# LaserConverterBoard.net
KiCad netlist of a schematic drawn in EAGLE
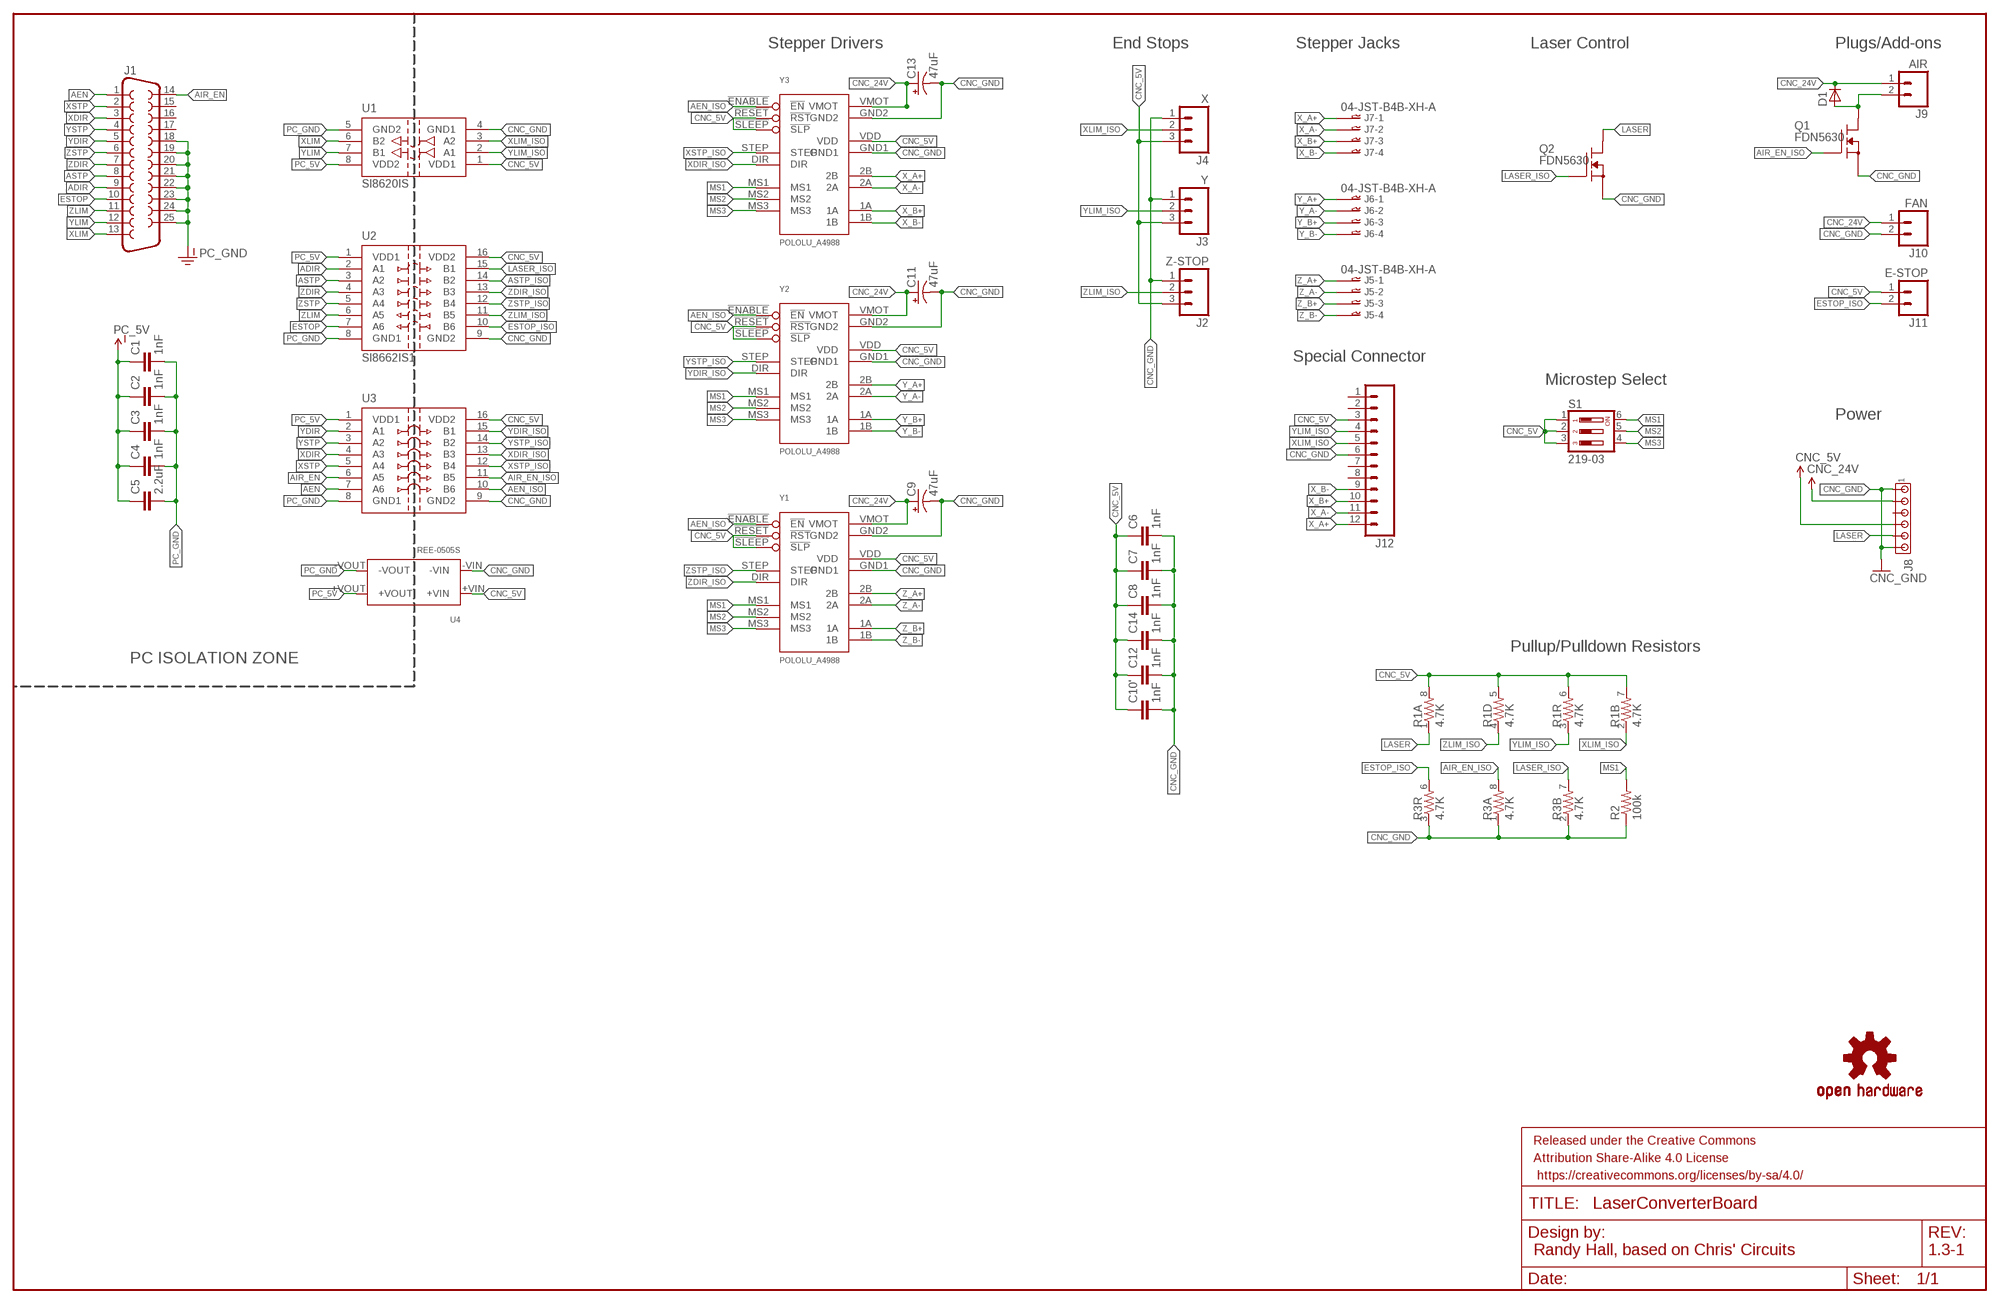
[diagram p0: schematic, sheet 1]

(export (version "E")
  (design (tool "Eeschema 10.0.6"))
  (components
    (comp (ref "C1")
      (value "1nF")
      (footprint "eagle-import:0603-CAP")
      (libsource (lib "eagle-import") (part "1NF/1000PF-50V-10%(0603)"))
    )
    (comp (ref "C2")
      (value "1nF")
      (footprint "eagle-import:0603-CAP")
      (libsource (lib "eagle-import") (part "1NF/1000PF-50V-10%(0603)"))
    )
    (comp (ref "C3")
      (value "1nF")
      (footprint "eagle-import:0603-CAP")
      (libsource (lib "eagle-import") (part "1NF/1000PF-50V-10%(0603)"))
    )
    (comp (ref "C4")
      (value "1nF")
      (footprint "eagle-import:0603-CAP")
      (libsource (lib "eagle-import") (part "1NF/1000PF-50V-10%(0603)"))
    )
    (comp (ref "C5")
      (value "2.2uF")
      (footprint "eagle-import:0603-CAP")
      (libsource (lib "eagle-import") (part "1NF/1000PF-50V-10%(0603)"))
    )
    (comp (ref "C6")
      (value "1nF")
      (footprint "eagle-import:0603-CAP")
      (libsource (lib "eagle-import") (part "1NF/1000PF-50V-10%(0603)"))
    )
    (comp (ref "C7")
      (value "1nF")
      (footprint "eagle-import:0603-CAP")
      (libsource (lib "eagle-import") (part "1NF/1000PF-50V-10%(0603)"))
    )
    (comp (ref "C8")
      (value "1nF")
      (footprint "eagle-import:0603-CAP")
      (libsource (lib "eagle-import") (part "1NF/1000PF-50V-10%(0603)"))
    )
    (comp (ref "C9")
      (value "47uF")
      (footprint "eagle-import:PANASONIC_E")
      (libsource (lib "eagle-import") (part "CPOL-USE"))
    )
    (comp (ref "C10'")
      (value "1nF")
      (footprint "eagle-import:0603-CAP")
      (libsource (lib "eagle-import") (part "1NF/1000PF-50V-10%(0603)"))
    )
    (comp (ref "C11")
      (value "47uF")
      (footprint "eagle-import:PANASONIC_E")
      (libsource (lib "eagle-import") (part "CPOL-USE"))
    )
    (comp (ref "C12")
      (value "1nF")
      (footprint "eagle-import:0603-CAP")
      (libsource (lib "eagle-import") (part "1NF/1000PF-50V-10%(0603)"))
    )
    (comp (ref "C13")
      (value "47uF")
      (footprint "eagle-import:PANASONIC_E")
      (libsource (lib "eagle-import") (part "CPOL-USE"))
    )
    (comp (ref "C14")
      (value "1nF")
      (footprint "eagle-import:0603-CAP")
      (libsource (lib "eagle-import") (part "1NF/1000PF-50V-10%(0603)"))
    )
    (comp (ref "D1")
      (value "D-SOD123")
      (footprint "eagle-import:SOD123")
      (libsource (lib "eagle-import") (part "D-SOD123"))
    )
    (comp (ref "FRAME1")
      (value "FRAME-LEDGER")
      (footprint "eagle-import:CREATIVE_COMMONS")
      (libsource (lib "eagle-import") (part "FRAME-LEDGER"))
    )
    (comp (ref "J1")
      (value "F25HP")
      (footprint "eagle-import:F25HP")
      (libsource (lib "eagle-import") (part "F25HP"))
    )
    (comp (ref "J2")
      (value "Z-STOP")
      (footprint "eagle-import:1X03")
      (libsource (lib "eagle-import") (part "M03PTH"))
    )
    (comp (ref "J3")
      (value "Y")
      (footprint "eagle-import:1X03")
      (libsource (lib "eagle-import") (part "M03PTH"))
    )
    (comp (ref "J4")
      (value "X")
      (footprint "eagle-import:1X03")
      (libsource (lib "eagle-import") (part "M03PTH"))
    )
    (comp (ref "J5")
      (value "04-JST-B4B-XH-A")
      (footprint "eagle-import:B4B-XH")
      (libsource (lib "eagle-import") (part "04-JST-B4B-XH-A"))
    )
    (comp (ref "J6")
      (value "04-JST-B4B-XH-A")
      (footprint "eagle-import:B4B-XH")
      (libsource (lib "eagle-import") (part "04-JST-B4B-XH-A"))
    )
    (comp (ref "J7")
      (value "04-JST-B4B-XH-A")
      (footprint "eagle-import:B4B-XH")
      (libsource (lib "eagle-import") (part "04-JST-B4B-XH-A"))
    )
    (comp (ref "J8")
      (value "MTA06-156")
      (footprint "eagle-import:1X6MTA")
      (libsource (lib "eagle-import") (part "MTA06-156"))
    )
    (comp (ref "J9")
      (value "AIR")
      (footprint "eagle-import:1X02")
      (libsource (lib "eagle-import") (part "M02PTH"))
    )
    (comp (ref "J10")
      (value "FAN")
      (footprint "eagle-import:1X02")
      (libsource (lib "eagle-import") (part "M02PTH"))
    )
    (comp (ref "J11")
      (value "E-STOP")
      (footprint "eagle-import:1X02")
      (libsource (lib "eagle-import") (part "M02PTH"))
    )
    (comp (ref "J12")
      (value "M12")
      (footprint "eagle-import:12P")
      (libsource (lib "eagle-import") (part "M12"))
    )
    (comp (ref "LOGO1")
      (value "OSHW-LOGOS")
      (footprint "eagle-import:OSHW-LOGO-S")
      (libsource (lib "eagle-import") (part "OSHW-LOGOS"))
    )
    (comp (ref "Q1")
      (value "FDN5630")
      (footprint "eagle-import:SOT23")
      (libsource (lib "eagle-import") (part "FDN5630"))
    )
    (comp (ref "Q2")
      (value "FDN5630")
      (footprint "eagle-import:SOT23")
      (libsource (lib "eagle-import") (part "FDN5630"))
    )
    (comp (ref "R1")
      (value "4.7K")
      (footprint "eagle-import:0603-ARV")
      (libsource (lib "eagle-import") (part "RESISTOR-ARRAY0603-ARV"))
    )
    (comp (ref "R2")
      (value "100k")
      (footprint "eagle-import:0603-RES")
      (libsource (lib "eagle-import") (part "100KOHM1/10W1%(0603)"))
    )
    (comp (ref "R3")
      (value "4.7K")
      (footprint "eagle-import:0603-ARV")
      (libsource (lib "eagle-import") (part "RESISTOR-ARRAY0603-ARV"))
    )
    (comp (ref "S1")
      (value "219-03")
      (footprint "eagle-import:CTS-219-03")
      (libsource (lib "eagle-import") (part "219-03"))
    )
    (comp (ref "U1")
      (value "SI8620IS")
      (footprint "eagle-import:SO08")
      (libsource (lib "eagle-import") (part "SI8620IS"))
    )
    (comp (ref "U2")
      (value "SI8662IS1")
      (footprint "eagle-import:SO16")
      (libsource (lib "eagle-import") (part "SI8462IS1"))
    )
    (comp (ref "U3")
      (value "SI8460IS1")
      (footprint "eagle-import:SO16")
      (libsource (lib "eagle-import") (part "SI8460IS1"))
    )
    (comp (ref "U4")
      (value "REE-0505S")
      (footprint "eagle-import:SIP7")
      (libsource (lib "eagle-import") (part "REE-0505S"))
    )
    (comp (ref "Y1")
      (value "POLOLU_A4988")
      (footprint "eagle-import:POLOLU_STEPPER_DRIVER")
      (libsource (lib "eagle-import") (part "POLOLU_A4988"))
    )
    (comp (ref "Y2")
      (value "POLOLU_A4988")
      (footprint "eagle-import:POLOLU_STEPPER_DRIVER")
      (libsource (lib "eagle-import") (part "POLOLU_A4988"))
    )
    (comp (ref "Y3")
      (value "POLOLU_A4988")
      (footprint "eagle-import:POLOLU_STEPPER_DRIVER")
      (libsource (lib "eagle-import") (part "POLOLU_A4988"))
    )
  )
  (nets
    (net (code "1") (name "ADIR") (class "Default")
      (node (ref "J1") (pin "9") (pinfunction "9_9") (pintype "passive"))
      (node (ref "U2") (pin "2") (pinfunction "A1_2") (pintype "input"))
    )
    (net (code "2") (name "AEN") (class "Default")
      (node (ref "J1") (pin "1") (pinfunction "1_1") (pintype "passive"))
      (node (ref "U3") (pin "7") (pinfunction "A6_7") (pintype "input"))
    )
    (net (code "3") (name "AEN_ISO") (class "Default")
      (node (ref "U3") (pin "10") (pinfunction "B6_10") (pintype "output"))
      (node (ref "Y1") (pin "!ENABLE") (pinfunction "~{EN}_!ENABLE") (pintype "input"))
      (node (ref "Y2") (pin "!ENABLE") (pinfunction "~{EN}_!ENABLE") (pintype "input"))
      (node (ref "Y3") (pin "!ENABLE") (pinfunction "~{EN}_!ENABLE") (pintype "input"))
    )
    (net (code "4") (name "AIR_EN") (class "Default")
      (node (ref "J1") (pin "14") (pinfunction "14_14") (pintype "passive"))
      (node (ref "U3") (pin "6") (pinfunction "A5_6") (pintype "input"))
    )
    (net (code "5") (name "AIR_EN_ISO") (class "Default")
      (node (ref "Q1") (pin "1") (pinfunction "G_1") (pintype "passive"))
      (node (ref "R3") (pin "8") (pinfunction "2_8") (pintype "passive"))
      (node (ref "U3") (pin "11") (pinfunction "B5_11") (pintype "output"))
    )
    (net (code "6") (name "ASTP") (class "Default")
      (node (ref "J1") (pin "8") (pinfunction "8_8") (pintype "passive"))
      (node (ref "U2") (pin "3") (pinfunction "A2_3") (pintype "input"))
    )
    (net (code "7") (name "ASTP_ISO") (class "Default")
      (node (ref "U2") (pin "14") (pinfunction "B2_14") (pintype "output"))
    )
    (net (code "8") (name "CNC_5V") (class "Default")
      (node (ref "C10'") (pin "1") (pinfunction "1_1") (pintype "passive"))
      (node (ref "C12") (pin "1") (pinfunction "1_1") (pintype "passive"))
      (node (ref "C14") (pin "1") (pinfunction "1_1") (pintype "passive"))
      (node (ref "C6") (pin "1") (pinfunction "1_1") (pintype "passive"))
      (node (ref "C7") (pin "1") (pinfunction "1_1") (pintype "passive"))
      (node (ref "C8") (pin "1") (pinfunction "1_1") (pintype "passive"))
      (node (ref "J11") (pin "1") (pinfunction "1_1") (pintype "passive"))
      (node (ref "J12") (pin "3") (pinfunction "3_3") (pintype "passive"))
      (node (ref "J2") (pin "3") (pinfunction "3_3") (pintype "passive"))
      (node (ref "J3") (pin "3") (pinfunction "3_3") (pintype "passive"))
      (node (ref "J4") (pin "3") (pinfunction "3_3") (pintype "passive"))
      (node (ref "J8") (pin "4") (pinfunction "4_4") (pintype "passive"))
      (node (ref "R1") (pin "5") (pinfunction "2_5") (pintype "passive"))
      (node (ref "R1") (pin "6") (pinfunction "2_6") (pintype "passive"))
      (node (ref "R1") (pin "7") (pinfunction "2_7") (pintype "passive"))
      (node (ref "R1") (pin "8") (pinfunction "2_8") (pintype "passive"))
      (node (ref "S1") (pin "1") (pinfunction "1_1") (pintype "passive"))
      (node (ref "S1") (pin "2") (pinfunction "2_2") (pintype "passive"))
      (node (ref "S1") (pin "3") (pinfunction "3_3") (pintype "passive"))
      (node (ref "U1") (pin "1") (pinfunction "VDD1_1") (pintype "power_in"))
      (node (ref "U2") (pin "16") (pinfunction "VDD2_16") (pintype "power_in"))
      (node (ref "U3") (pin "16") (pinfunction "VDD2_16") (pintype "power_in"))
      (node (ref "U4") (pin "+VIN") (pinfunction "+VIN_+VIN") (pintype "power_in"))
      (node (ref "Y1") (pin "!RESET") (pinfunction "~{RST}_!RESET") (pintype "input"))
      (node (ref "Y1") (pin "!SLEEP") (pinfunction "~{SLP}_!SLEEP") (pintype "input"))
      (node (ref "Y1") (pin "VDD") (pinfunction "VDD_VDD") (pintype "power_in"))
      (node (ref "Y2") (pin "!RESET") (pinfunction "~{RST}_!RESET") (pintype "input"))
      (node (ref "Y2") (pin "!SLEEP") (pinfunction "~{SLP}_!SLEEP") (pintype "input"))
      (node (ref "Y2") (pin "VDD") (pinfunction "VDD_VDD") (pintype "power_in"))
      (node (ref "Y3") (pin "!RESET") (pinfunction "~{RST}_!RESET") (pintype "input"))
      (node (ref "Y3") (pin "!SLEEP") (pinfunction "~{SLP}_!SLEEP") (pintype "input"))
      (node (ref "Y3") (pin "VDD") (pinfunction "VDD_VDD") (pintype "power_in"))
    )
    (net (code "9") (name "CNC_24V") (class "Default")
      (node (ref "C11") (pin "+") (pinfunction "+_+") (pintype "passive"))
      (node (ref "C13") (pin "+") (pinfunction "+_+") (pintype "passive"))
      (node (ref "C9") (pin "+") (pinfunction "+_+") (pintype "passive"))
      (node (ref "D1") (pin "1") (pinfunction "C_1") (pintype "passive"))
      (node (ref "J10") (pin "1") (pinfunction "1_1") (pintype "passive"))
      (node (ref "J8") (pin "2") (pinfunction "2_2") (pintype "passive"))
      (node (ref "J9") (pin "1") (pinfunction "1_1") (pintype "passive"))
      (node (ref "Y1") (pin "VMOT") (pinfunction "VMOT_VMOT") (pintype "power_in"))
      (node (ref "Y2") (pin "VMOT") (pinfunction "VMOT_VMOT") (pintype "power_in"))
      (node (ref "Y3") (pin "VMOT") (pinfunction "VMOT_VMOT") (pintype "power_in"))
    )
    (net (code "10") (name "CNC_GND") (class "Default")
      (node (ref "C10'") (pin "2") (pinfunction "2_2") (pintype "passive"))
      (node (ref "C11") (pin "-") (pinfunction "-_-") (pintype "passive"))
      (node (ref "C12") (pin "2") (pinfunction "2_2") (pintype "passive"))
      (node (ref "C13") (pin "-") (pinfunction "-_-") (pintype "passive"))
      (node (ref "C14") (pin "2") (pinfunction "2_2") (pintype "passive"))
      (node (ref "C6") (pin "2") (pinfunction "2_2") (pintype "passive"))
      (node (ref "C7") (pin "2") (pinfunction "2_2") (pintype "passive"))
      (node (ref "C8") (pin "2") (pinfunction "2_2") (pintype "passive"))
      (node (ref "C9") (pin "-") (pinfunction "-_-") (pintype "passive"))
      (node (ref "J10") (pin "2") (pinfunction "2_2") (pintype "passive"))
      (node (ref "J12") (pin "6") (pinfunction "6_6") (pintype "passive"))
      (node (ref "J2") (pin "1") (pinfunction "1_1") (pintype "passive"))
      (node (ref "J3") (pin "1") (pinfunction "1_1") (pintype "passive"))
      (node (ref "J4") (pin "1") (pinfunction "1_1") (pintype "passive"))
      (node (ref "J8") (pin "1") (pinfunction "1_1") (pintype "passive"))
      (node (ref "J8") (pin "6") (pinfunction "6_6") (pintype "passive"))
      (node (ref "Q1") (pin "2") (pinfunction "S_2") (pintype "passive"))
      (node (ref "Q2") (pin "2") (pinfunction "S_2") (pintype "passive"))
      (node (ref "R2") (pin "1") (pinfunction "1_1") (pintype "passive"))
      (node (ref "R3") (pin "1") (pinfunction "1_1") (pintype "passive"))
      (node (ref "R3") (pin "2") (pinfunction "1_2") (pintype "passive"))
      (node (ref "R3") (pin "3") (pinfunction "1_3") (pintype "passive"))
      (node (ref "U1") (pin "4") (pinfunction "GND1_4") (pintype "power_in"))
      (node (ref "U2") (pin "9") (pinfunction "GND2_9") (pintype "power_in"))
      (node (ref "U3") (pin "9") (pinfunction "GND2_9") (pintype "power_in"))
      (node (ref "U4") (pin "-VIN") (pinfunction "-VIN_-VIN") (pintype "power_in"))
      (node (ref "Y1") (pin "GND1") (pinfunction "GND1_GND1") (pintype "power_in"))
      (node (ref "Y1") (pin "GND2") (pinfunction "GND2_GND2") (pintype "power_in"))
      (node (ref "Y2") (pin "GND1") (pinfunction "GND1_GND1") (pintype "power_in"))
      (node (ref "Y2") (pin "GND2") (pinfunction "GND2_GND2") (pintype "power_in"))
      (node (ref "Y3") (pin "GND1") (pinfunction "GND1_GND1") (pintype "power_in"))
      (node (ref "Y3") (pin "GND2") (pinfunction "GND2_GND2") (pintype "power_in"))
    )
    (net (code "11") (name "ESTOP") (class "Default")
      (node (ref "J1") (pin "10") (pinfunction "10_10") (pintype "passive"))
      (node (ref "U2") (pin "7") (pinfunction "A6_7") (pintype "output"))
    )
    (net (code "12") (name "ESTOP_ISO") (class "Default")
      (node (ref "J11") (pin "2") (pinfunction "2_2") (pintype "passive"))
      (node (ref "R3") (pin "6") (pinfunction "2_6") (pintype "passive"))
      (node (ref "U2") (pin "10") (pinfunction "B6_10") (pintype "input"))
    )
    (net (code "13") (name "LASER") (class "Default")
      (node (ref "J8") (pin "5") (pinfunction "5_5") (pintype "passive"))
      (node (ref "Q2") (pin "3") (pinfunction "D_3") (pintype "passive"))
      (node (ref "R1") (pin "1") (pinfunction "1_1") (pintype "passive"))
    )
    (net (code "14") (name "LASER_ISO") (class "Default")
      (node (ref "Q2") (pin "1") (pinfunction "G_1") (pintype "passive"))
      (node (ref "R3") (pin "7") (pinfunction "2_7") (pintype "passive"))
      (node (ref "U2") (pin "15") (pinfunction "B1_15") (pintype "output"))
    )
    (net (code "15") (name "MS1") (class "Default")
      (node (ref "R2") (pin "2") (pinfunction "2_2") (pintype "passive"))
      (node (ref "S1") (pin "6") (pinfunction "6_6") (pintype "passive"))
      (node (ref "Y1") (pin "MS1") (pinfunction "MS1_MS1") (pintype "input"))
      (node (ref "Y2") (pin "MS1") (pinfunction "MS1_MS1") (pintype "input"))
      (node (ref "Y3") (pin "MS1") (pinfunction "MS1_MS1") (pintype "input"))
    )
    (net (code "16") (name "MS2") (class "Default")
      (node (ref "S1") (pin "5") (pinfunction "5_5") (pintype "passive"))
      (node (ref "Y1") (pin "MS2") (pinfunction "MS2_MS2") (pintype "input"))
      (node (ref "Y2") (pin "MS2") (pinfunction "MS2_MS2") (pintype "input"))
      (node (ref "Y3") (pin "MS2") (pinfunction "MS2_MS2") (pintype "input"))
    )
    (net (code "17") (name "MS3") (class "Default")
      (node (ref "S1") (pin "4") (pinfunction "4_4") (pintype "passive"))
      (node (ref "Y1") (pin "MS3") (pinfunction "MS3_MS3") (pintype "input"))
      (node (ref "Y2") (pin "MS3") (pinfunction "MS3_MS3") (pintype "input"))
      (node (ref "Y3") (pin "MS3") (pinfunction "MS3_MS3") (pintype "input"))
    )
    (net (code "18") (name "Net-(D1-A)") (class "Default")
      (node (ref "D1") (pin "2") (pinfunction "A_2") (pintype "passive"))
      (node (ref "J9") (pin "2") (pinfunction "2_2") (pintype "passive"))
      (node (ref "Q1") (pin "3") (pinfunction "D_3") (pintype "passive"))
    )
    (net (code "19") (name "PC_5V") (class "Default")
      (node (ref "C1") (pin "1") (pinfunction "1_1") (pintype "passive"))
      (node (ref "C2") (pin "1") (pinfunction "1_1") (pintype "passive"))
      (node (ref "C3") (pin "1") (pinfunction "1_1") (pintype "passive"))
      (node (ref "C4") (pin "1") (pinfunction "1_1") (pintype "passive"))
      (node (ref "C5") (pin "1") (pinfunction "1_1") (pintype "passive"))
      (node (ref "U1") (pin "8") (pinfunction "VDD2_8") (pintype "power_in"))
      (node (ref "U2") (pin "1") (pinfunction "VDD1_1") (pintype "power_in"))
      (node (ref "U3") (pin "1") (pinfunction "VDD1_1") (pintype "power_in"))
      (node (ref "U4") (pin "+VOUT") (pinfunction "+VOUT_+VOUT") (pintype "power_in"))
    )
    (net (code "20") (name "PC_GND") (class "Default")
      (node (ref "C1") (pin "2") (pinfunction "2_2") (pintype "passive"))
      (node (ref "C2") (pin "2") (pinfunction "2_2") (pintype "passive"))
      (node (ref "C3") (pin "2") (pinfunction "2_2") (pintype "passive"))
      (node (ref "C4") (pin "2") (pinfunction "2_2") (pintype "passive"))
      (node (ref "C5") (pin "2") (pinfunction "2_2") (pintype "passive"))
      (node (ref "J1") (pin "18") (pinfunction "18_18") (pintype "passive"))
      (node (ref "J1") (pin "19") (pinfunction "19_19") (pintype "passive"))
      (node (ref "J1") (pin "20") (pinfunction "20_20") (pintype "passive"))
      (node (ref "J1") (pin "21") (pinfunction "21_21") (pintype "passive"))
      (node (ref "J1") (pin "22") (pinfunction "22_22") (pintype "passive"))
      (node (ref "J1") (pin "23") (pinfunction "23_23") (pintype "passive"))
      (node (ref "J1") (pin "24") (pinfunction "24_24") (pintype "passive"))
      (node (ref "J1") (pin "25") (pinfunction "25_25") (pintype "passive"))
      (node (ref "U1") (pin "5") (pinfunction "GND2_5") (pintype "power_in"))
      (node (ref "U2") (pin "8") (pinfunction "GND1_8") (pintype "power_in"))
      (node (ref "U3") (pin "8") (pinfunction "GND1_8") (pintype "power_in"))
      (node (ref "U4") (pin "-VOUT") (pinfunction "-VOUT_-VOUT") (pintype "power_in"))
    )
    (net (code "21") (name "XDIR") (class "Default")
      (node (ref "J1") (pin "3") (pinfunction "3_3") (pintype "passive"))
      (node (ref "U3") (pin "4") (pinfunction "A3_4") (pintype "input"))
    )
    (net (code "22") (name "XDIR_ISO") (class "Default")
      (node (ref "U3") (pin "13") (pinfunction "B3_13") (pintype "output"))
      (node (ref "Y3") (pin "DIR") (pinfunction "DIR_DIR") (pintype "input"))
    )
    (net (code "23") (name "XLIM") (class "Default")
      (node (ref "J1") (pin "13") (pinfunction "13_13") (pintype "passive"))
      (node (ref "U1") (pin "6") (pinfunction "B2_6") (pintype "output"))
    )
    (net (code "24") (name "XLIM_ISO") (class "Default")
      (node (ref "J12") (pin "5") (pinfunction "5_5") (pintype "passive"))
      (node (ref "J4") (pin "2") (pinfunction "2_2") (pintype "passive"))
      (node (ref "R1") (pin "2") (pinfunction "1_2") (pintype "passive"))
      (node (ref "U1") (pin "3") (pinfunction "A2_3") (pintype "input"))
    )
    (net (code "25") (name "XSTP") (class "Default")
      (node (ref "J1") (pin "2") (pinfunction "2_2") (pintype "passive"))
      (node (ref "U3") (pin "5") (pinfunction "A4_5") (pintype "input"))
    )
    (net (code "26") (name "XSTP_ISO") (class "Default")
      (node (ref "U3") (pin "12") (pinfunction "B4_12") (pintype "output"))
      (node (ref "Y3") (pin "STEP") (pinfunction "STEP_STEP") (pintype "input"))
    )
    (net (code "27") (name "X_A+") (class "Default")
      (node (ref "J12") (pin "12") (pinfunction "12_12") (pintype "passive"))
      (node (ref "J7") (pin "P$1") (pinfunction "1_P$1") (pintype "passive"))
      (node (ref "Y3") (pin "2B") (pinfunction "2B_2B") (pintype "output"))
    )
    (net (code "28") (name "X_A-") (class "Default")
      (node (ref "J12") (pin "11") (pinfunction "11_11") (pintype "passive"))
      (node (ref "J7") (pin "P$2") (pinfunction "1_P$2") (pintype "passive"))
      (node (ref "Y3") (pin "2A") (pinfunction "2A_2A") (pintype "output"))
    )
    (net (code "29") (name "X_B+") (class "Default")
      (node (ref "J12") (pin "10") (pinfunction "10_10") (pintype "passive"))
      (node (ref "J7") (pin "P$3") (pinfunction "1_P$3") (pintype "passive"))
      (node (ref "Y3") (pin "1A") (pinfunction "1A_1A") (pintype "output"))
    )
    (net (code "30") (name "X_B-") (class "Default")
      (node (ref "J12") (pin "9") (pinfunction "9_9") (pintype "passive"))
      (node (ref "J7") (pin "P$4") (pinfunction "1_P$4") (pintype "passive"))
      (node (ref "Y3") (pin "1B") (pinfunction "1B_1B") (pintype "output"))
    )
    (net (code "31") (name "YDIR") (class "Default")
      (node (ref "J1") (pin "5") (pinfunction "5_5") (pintype "passive"))
      (node (ref "U3") (pin "2") (pinfunction "A1_2") (pintype "input"))
    )
    (net (code "32") (name "YDIR_ISO") (class "Default")
      (node (ref "U3") (pin "15") (pinfunction "B1_15") (pintype "output"))
      (node (ref "Y2") (pin "DIR") (pinfunction "DIR_DIR") (pintype "input"))
    )
    (net (code "33") (name "YLIM") (class "Default")
      (node (ref "J1") (pin "12") (pinfunction "12_12") (pintype "passive"))
      (node (ref "U1") (pin "7") (pinfunction "B1_7") (pintype "output"))
    )
    (net (code "34") (name "YLIM_ISO") (class "Default")
      (node (ref "J12") (pin "4") (pinfunction "4_4") (pintype "passive"))
      (node (ref "J3") (pin "2") (pinfunction "2_2") (pintype "passive"))
      (node (ref "R1") (pin "3") (pinfunction "1_3") (pintype "passive"))
      (node (ref "U1") (pin "2") (pinfunction "A1_2") (pintype "input"))
    )
    (net (code "35") (name "YSTP") (class "Default")
      (node (ref "J1") (pin "4") (pinfunction "4_4") (pintype "passive"))
      (node (ref "U3") (pin "3") (pinfunction "A2_3") (pintype "input"))
    )
    (net (code "36") (name "YSTP_ISO") (class "Default")
      (node (ref "U3") (pin "14") (pinfunction "B2_14") (pintype "output"))
      (node (ref "Y2") (pin "STEP") (pinfunction "STEP_STEP") (pintype "input"))
    )
    (net (code "37") (name "Y_A+") (class "Default")
      (node (ref "J6") (pin "P$1") (pinfunction "1_P$1") (pintype "passive"))
      (node (ref "Y2") (pin "2B") (pinfunction "2B_2B") (pintype "output"))
    )
    (net (code "38") (name "Y_A-") (class "Default")
      (node (ref "J6") (pin "P$2") (pinfunction "1_P$2") (pintype "passive"))
      (node (ref "Y2") (pin "2A") (pinfunction "2A_2A") (pintype "output"))
    )
    (net (code "39") (name "Y_B+") (class "Default")
      (node (ref "J6") (pin "P$3") (pinfunction "1_P$3") (pintype "passive"))
      (node (ref "Y2") (pin "1A") (pinfunction "1A_1A") (pintype "output"))
    )
    (net (code "40") (name "Y_B-") (class "Default")
      (node (ref "J6") (pin "P$4") (pinfunction "1_P$4") (pintype "passive"))
      (node (ref "Y2") (pin "1B") (pinfunction "1B_1B") (pintype "output"))
    )
    (net (code "41") (name "ZDIR") (class "Default")
      (node (ref "J1") (pin "7") (pinfunction "7_7") (pintype "passive"))
      (node (ref "U2") (pin "4") (pinfunction "A3_4") (pintype "input"))
    )
    (net (code "42") (name "ZDIR_ISO") (class "Default")
      (node (ref "U2") (pin "13") (pinfunction "B3_13") (pintype "output"))
      (node (ref "Y1") (pin "DIR") (pinfunction "DIR_DIR") (pintype "input"))
    )
    (net (code "43") (name "ZLIM") (class "Default")
      (node (ref "J1") (pin "11") (pinfunction "11_11") (pintype "passive"))
      (node (ref "U2") (pin "6") (pinfunction "A5_6") (pintype "output"))
    )
    (net (code "44") (name "ZLIM_ISO") (class "Default")
      (node (ref "J2") (pin "2") (pinfunction "2_2") (pintype "passive"))
      (node (ref "R1") (pin "4") (pinfunction "1_4") (pintype "passive"))
      (node (ref "U2") (pin "11") (pinfunction "B5_11") (pintype "input"))
    )
    (net (code "45") (name "ZSTP") (class "Default")
      (node (ref "J1") (pin "6") (pinfunction "6_6") (pintype "passive"))
      (node (ref "U2") (pin "5") (pinfunction "A4_5") (pintype "input"))
    )
    (net (code "46") (name "ZSTP_ISO") (class "Default")
      (node (ref "U2") (pin "12") (pinfunction "B4_12") (pintype "output"))
      (node (ref "Y1") (pin "STEP") (pinfunction "STEP_STEP") (pintype "input"))
    )
    (net (code "47") (name "Z_A+") (class "Default")
      (node (ref "J5") (pin "P$1") (pinfunction "1_P$1") (pintype "passive"))
      (node (ref "Y1") (pin "2B") (pinfunction "2B_2B") (pintype "output"))
    )
    (net (code "48") (name "Z_A-") (class "Default")
      (node (ref "J5") (pin "P$2") (pinfunction "1_P$2") (pintype "passive"))
      (node (ref "Y1") (pin "2A") (pinfunction "2A_2A") (pintype "output"))
    )
    (net (code "49") (name "Z_B+") (class "Default")
      (node (ref "J5") (pin "P$3") (pinfunction "1_P$3") (pintype "passive"))
      (node (ref "Y1") (pin "1A") (pinfunction "1A_1A") (pintype "output"))
    )
    (net (code "50") (name "Z_B-") (class "Default")
      (node (ref "J5") (pin "P$4") (pinfunction "1_P$4") (pintype "passive"))
      (node (ref "Y1") (pin "1B") (pinfunction "1B_1B") (pintype "output"))
    )
    (net (code "51") (name "unconnected-(J1-Pad15)") (class "Default")
      (node (ref "J1") (pin "15") (pinfunction "15_15") (pintype "passive"))
    )
    (net (code "52") (name "unconnected-(J1-Pad16)") (class "Default")
      (node (ref "J1") (pin "16") (pinfunction "16_16") (pintype "passive"))
    )
    (net (code "53") (name "unconnected-(J1-Pad17)") (class "Default")
      (node (ref "J1") (pin "17") (pinfunction "17_17") (pintype "passive"))
    )
    (net (code "54") (name "unconnected-(J8-Pad3)") (class "Default")
      (node (ref "J8") (pin "3") (pinfunction "3_3") (pintype "passive"))
    )
    (net (code "55") (name "unconnected-(J12-Pad1)") (class "Default")
      (node (ref "J12") (pin "1") (pinfunction "1_1") (pintype "passive"))
    )
    (net (code "56") (name "unconnected-(J12-Pad2)") (class "Default")
      (node (ref "J12") (pin "2") (pinfunction "2_2") (pintype "passive"))
    )
    (net (code "57") (name "unconnected-(J12-Pad7)") (class "Default")
      (node (ref "J12") (pin "7") (pinfunction "7_7") (pintype "passive"))
    )
    (net (code "58") (name "unconnected-(J12-Pad8)") (class "Default")
      (node (ref "J12") (pin "8") (pinfunction "8_8") (pintype "passive"))
    )
  )
)
